# MAXIM-ADC.net
KiCad netlist of a schematic drawn in Altium Designer
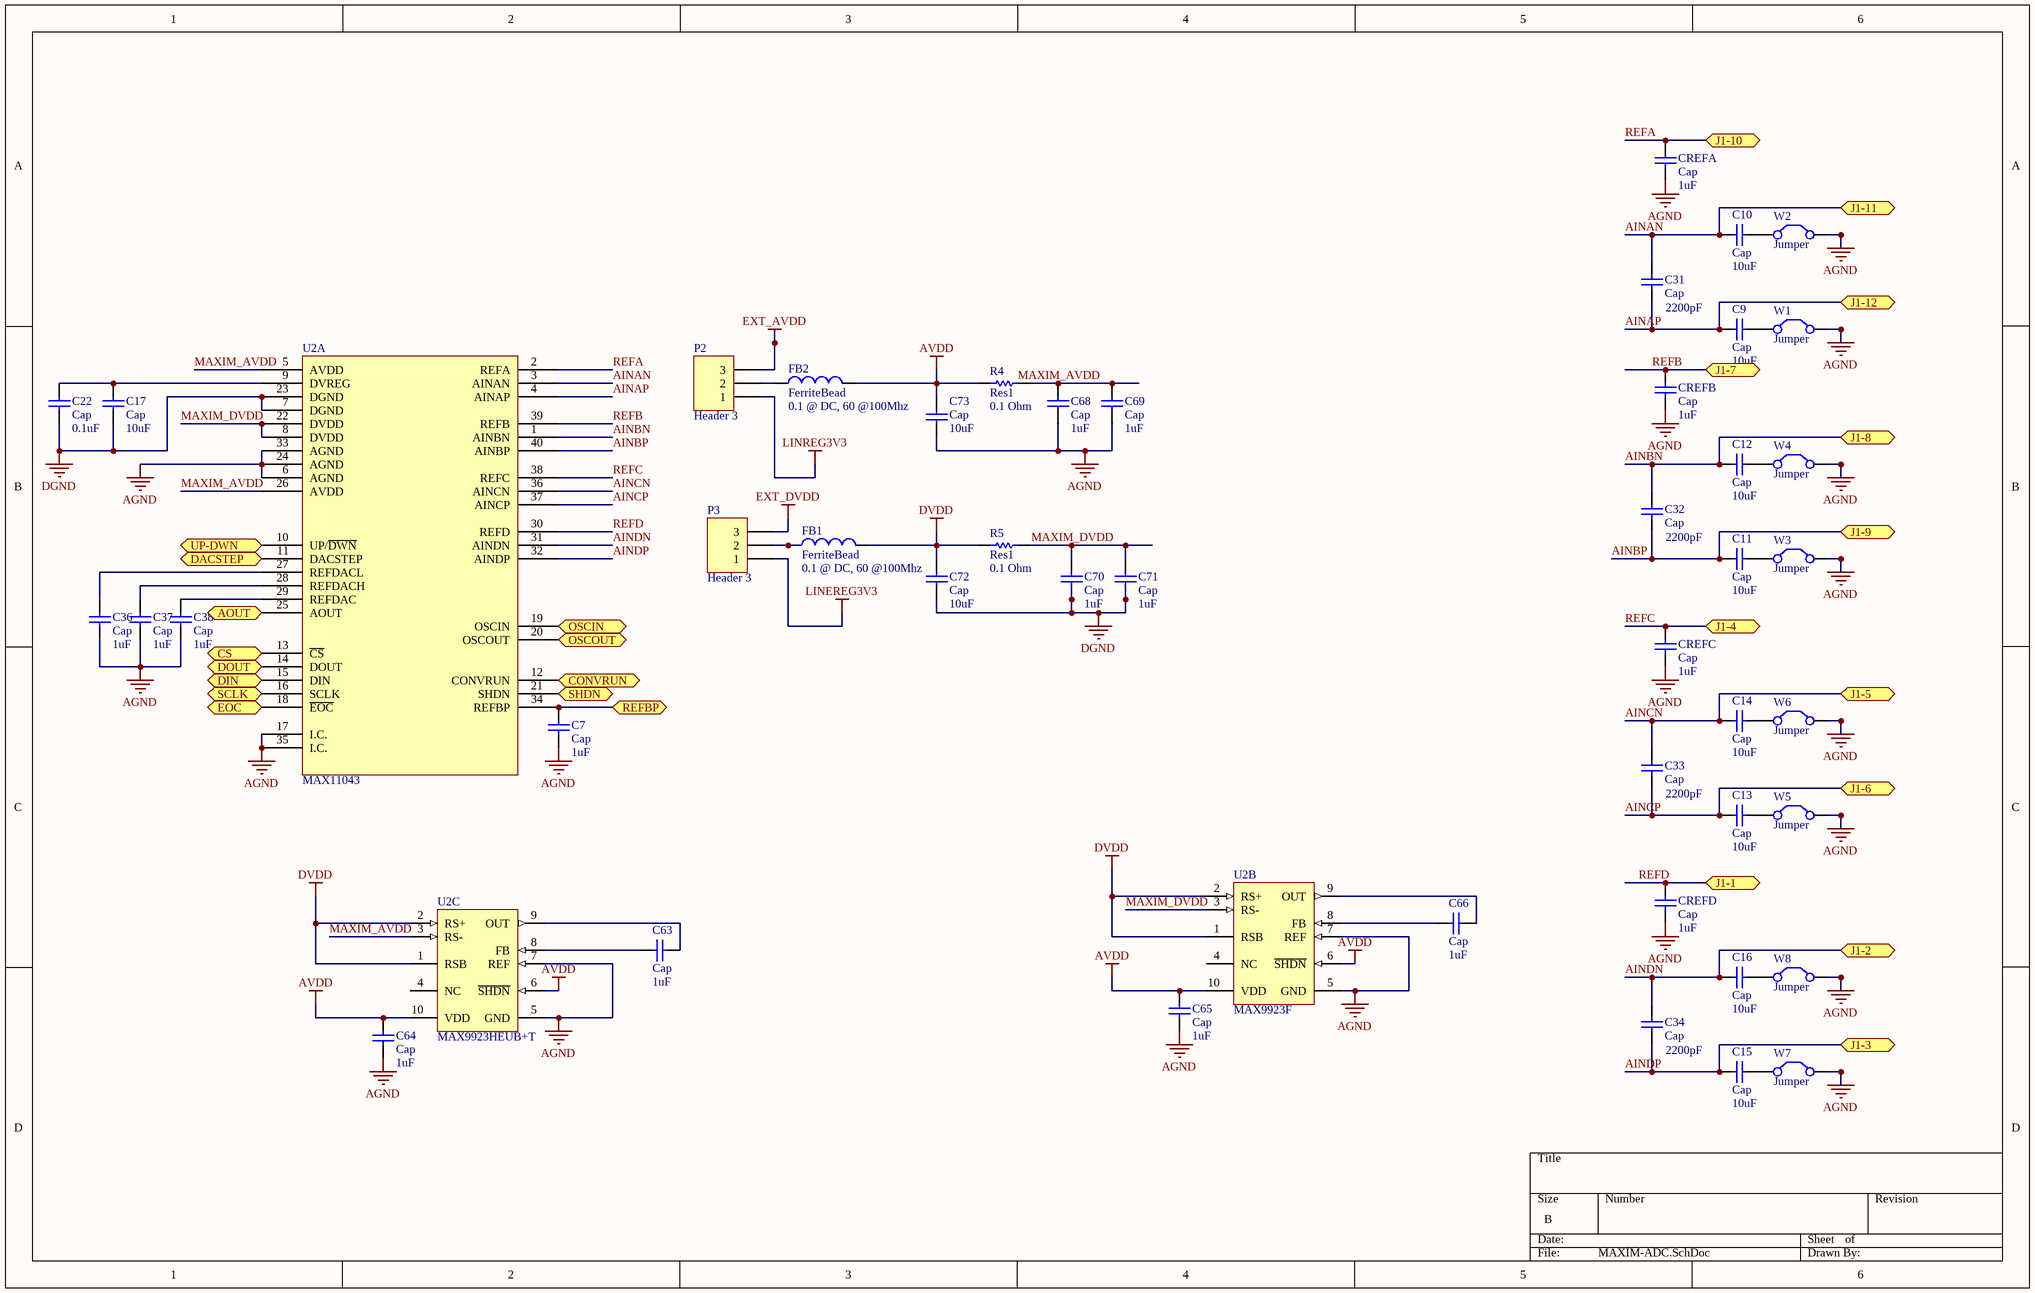
[diagram p0: MAXIM-ADC.SchDoc]

(export (version "E")
  (design (tool "Eeschema 10.0.6"))
  (components
    (comp (ref "C7")
      (value "Cap")
      (footprint "RAD-0.3")
      (description "Capacitor")
      (fields (field (name "ALTIUM_VALUE") "1uF") (field (name "PUBLISHER") "Altium Limited"))
      (libsource (lib "Miscellaneous Devices") (part "Cap"))
    )
    (comp (ref "C9")
      (value "Cap")
      (footprint "RAD-0.3")
      (description "Capacitor")
      (fields (field (name "ALTIUM_VALUE") "10uF") (field (name "PUBLISHER") "Altium Limited"))
      (libsource (lib "Miscellaneous Devices") (part "Cap"))
    )
    (comp (ref "C10")
      (value "Cap")
      (footprint "RAD-0.3")
      (description "Capacitor")
      (fields (field (name "ALTIUM_VALUE") "10uF") (field (name "PUBLISHER") "Altium Limited"))
      (libsource (lib "Miscellaneous Devices") (part "Cap"))
    )
    (comp (ref "C11")
      (value "Cap")
      (footprint "RAD-0.3")
      (description "Capacitor")
      (fields (field (name "ALTIUM_VALUE") "10uF") (field (name "PUBLISHER") "Altium Limited"))
      (libsource (lib "Miscellaneous Devices") (part "Cap"))
    )
    (comp (ref "C12")
      (value "Cap")
      (footprint "RAD-0.3")
      (description "Capacitor")
      (fields (field (name "ALTIUM_VALUE") "10uF") (field (name "PUBLISHER") "Altium Limited"))
      (libsource (lib "Miscellaneous Devices") (part "Cap"))
    )
    (comp (ref "C13")
      (value "Cap")
      (footprint "RAD-0.3")
      (description "Capacitor")
      (fields (field (name "ALTIUM_VALUE") "10uF") (field (name "PUBLISHER") "Altium Limited"))
      (libsource (lib "Miscellaneous Devices") (part "Cap"))
    )
    (comp (ref "C14")
      (value "Cap")
      (footprint "RAD-0.3")
      (description "Capacitor")
      (fields (field (name "ALTIUM_VALUE") "10uF") (field (name "PUBLISHER") "Altium Limited"))
      (libsource (lib "Miscellaneous Devices") (part "Cap"))
    )
    (comp (ref "C15")
      (value "Cap")
      (footprint "RAD-0.3")
      (description "Capacitor")
      (fields (field (name "ALTIUM_VALUE") "10uF") (field (name "PUBLISHER") "Altium Limited"))
      (libsource (lib "Miscellaneous Devices") (part "Cap"))
    )
    (comp (ref "C16")
      (value "Cap")
      (footprint "RAD-0.3")
      (description "Capacitor")
      (fields (field (name "ALTIUM_VALUE") "10uF") (field (name "PUBLISHER") "Altium Limited"))
      (libsource (lib "Miscellaneous Devices") (part "Cap"))
    )
    (comp (ref "C17")
      (value "Cap")
      (footprint "RAD-0.3")
      (description "Capacitor")
      (fields (field (name "ALTIUM_VALUE") "10uF") (field (name "PUBLISHER") "Altium Limited"))
      (libsource (lib "Miscellaneous Devices") (part "Cap"))
    )
    (comp (ref "C22")
      (value "Cap")
      (footprint "RAD-0.3")
      (description "Capacitor")
      (fields (field (name "ALTIUM_VALUE") "0.1uF") (field (name "PUBLISHER") "Altium Limited"))
      (libsource (lib "Miscellaneous Devices") (part "Cap"))
    )
    (comp (ref "C31")
      (value "Cap")
      (footprint "RAD-0.3")
      (description "Capacitor")
      (fields (field (name "ALTIUM_VALUE") "2200pF") (field (name "PUBLISHER") "Altium Limited"))
      (libsource (lib "Miscellaneous Devices") (part "Cap"))
    )
    (comp (ref "C32")
      (value "Cap")
      (footprint "RAD-0.3")
      (description "Capacitor")
      (fields (field (name "ALTIUM_VALUE") "2200pF") (field (name "PUBLISHER") "Altium Limited"))
      (libsource (lib "Miscellaneous Devices") (part "Cap"))
    )
    (comp (ref "C33")
      (value "Cap")
      (footprint "RAD-0.3")
      (description "Capacitor")
      (fields (field (name "ALTIUM_VALUE") "2200pF") (field (name "PUBLISHER") "Altium Limited"))
      (libsource (lib "Miscellaneous Devices") (part "Cap"))
    )
    (comp (ref "C34")
      (value "Cap")
      (footprint "RAD-0.3")
      (description "Capacitor")
      (fields (field (name "ALTIUM_VALUE") "2200pF") (field (name "PUBLISHER") "Altium Limited"))
      (libsource (lib "Miscellaneous Devices") (part "Cap"))
    )
    (comp (ref "C36")
      (value "Cap")
      (footprint "RAD-0.3")
      (description "Capacitor")
      (fields (field (name "ALTIUM_VALUE") "1uF") (field (name "PUBLISHER") "Altium Limited"))
      (libsource (lib "Miscellaneous Devices") (part "Cap"))
    )
    (comp (ref "C37")
      (value "Cap")
      (footprint "RAD-0.3")
      (description "Capacitor")
      (fields (field (name "ALTIUM_VALUE") "1uF") (field (name "PUBLISHER") "Altium Limited"))
      (libsource (lib "Miscellaneous Devices") (part "Cap"))
    )
    (comp (ref "C38")
      (value "Cap")
      (footprint "RAD-0.3")
      (description "Capacitor")
      (fields (field (name "ALTIUM_VALUE") "1uF") (field (name "PUBLISHER") "Altium Limited"))
      (libsource (lib "Miscellaneous Devices") (part "Cap"))
    )
    (comp (ref "C63")
      (value "Cap")
      (footprint "RAD-0.3")
      (description "Capacitor")
      (fields (field (name "ALTIUM_VALUE") "1uF") (field (name "PUBLISHER") "Altium Limited"))
      (libsource (lib "Miscellaneous Devices") (part "Cap"))
    )
    (comp (ref "C64")
      (value "Cap")
      (footprint "RAD-0.3")
      (description "Capacitor")
      (fields (field (name "ALTIUM_VALUE") "1uF") (field (name "PUBLISHER") "Altium Limited"))
      (libsource (lib "Miscellaneous Devices") (part "Cap"))
    )
    (comp (ref "C65")
      (value "Cap")
      (footprint "RAD-0.3")
      (description "Capacitor")
      (fields (field (name "ALTIUM_VALUE") "1uF") (field (name "PUBLISHER") "Altium Limited"))
      (libsource (lib "Miscellaneous Devices") (part "Cap"))
    )
    (comp (ref "C66")
      (value "Cap")
      (footprint "RAD-0.3")
      (description "Capacitor")
      (fields (field (name "ALTIUM_VALUE") "1uF") (field (name "PUBLISHER") "Altium Limited"))
      (libsource (lib "Miscellaneous Devices") (part "Cap"))
    )
    (comp (ref "C68")
      (value "Cap")
      (footprint "0603")
      (description "Capacitor")
      (fields (field (name "ALTIUM_VALUE") "1uF") (field (name "PUBLISHER") "Altium Limited"))
      (libsource (lib "Miscellaneous Devices") (part "Cap"))
    )
    (comp (ref "C69")
      (value "Cap")
      (footprint "RAD-0.3")
      (description "Capacitor")
      (fields (field (name "ALTIUM_VALUE") "1uF") (field (name "PUBLISHER") "Altium Limited"))
      (libsource (lib "Miscellaneous Devices") (part "Cap"))
    )
    (comp (ref "C70")
      (value "Cap")
      (footprint "RAD-0.3")
      (description "Capacitor")
      (fields (field (name "ALTIUM_VALUE") "1uF") (field (name "PUBLISHER") "Altium Limited"))
      (libsource (lib "Miscellaneous Devices") (part "Cap"))
    )
    (comp (ref "C71")
      (value "Cap")
      (footprint "RAD-0.3")
      (description "Capacitor")
      (fields (field (name "ALTIUM_VALUE") "1uF") (field (name "PUBLISHER") "Altium Limited"))
      (libsource (lib "Miscellaneous Devices") (part "Cap"))
    )
    (comp (ref "C72")
      (value "Cap")
      (footprint "RAD-0.3")
      (description "Capacitor")
      (fields (field (name "ALTIUM_VALUE") "10uF") (field (name "PUBLISHER") "Altium Limited"))
      (libsource (lib "Miscellaneous Devices") (part "Cap"))
    )
    (comp (ref "C73")
      (value "Cap")
      (footprint "RAD-0.3")
      (description "Capacitor")
      (fields (field (name "ALTIUM_VALUE") "10uF") (field (name "PUBLISHER") "Altium Limited"))
      (libsource (lib "Miscellaneous Devices") (part "Cap"))
    )
    (comp (ref "CREFA")
      (value "Cap")
      (footprint "RAD-0.3")
      (description "Capacitor")
      (fields (field (name "ALTIUM_VALUE") "1uF") (field (name "PUBLISHER") "Altium Limited"))
      (libsource (lib "Miscellaneous Devices") (part "Cap"))
    )
    (comp (ref "CREFB")
      (value "Cap")
      (footprint "RAD-0.3")
      (description "Capacitor")
      (fields (field (name "ALTIUM_VALUE") "1uF") (field (name "PUBLISHER") "Altium Limited"))
      (libsource (lib "Miscellaneous Devices") (part "Cap"))
    )
    (comp (ref "CREFC")
      (value "Cap")
      (footprint "RAD-0.3")
      (description "Capacitor")
      (fields (field (name "ALTIUM_VALUE") "1uF") (field (name "PUBLISHER") "Altium Limited"))
      (libsource (lib "Miscellaneous Devices") (part "Cap"))
    )
    (comp (ref "CREFD")
      (value "Cap")
      (footprint "RAD-0.3")
      (description "Capacitor")
      (fields (field (name "ALTIUM_VALUE") "1uF") (field (name "PUBLISHER") "Altium Limited"))
      (libsource (lib "Miscellaneous Devices") (part "Cap"))
    )
    (comp (ref "FB1")
      (value "FerriteBead")
      (footprint "0603")
      (description "Inductor")
      (fields
        (field (name "ALTIUM_VALUE") "0.1 @ DC, 60 @100Mhz")
        (field (name "PUBLISHER") "Altium Limited")
      )
      (libsource (lib "Miscellaneous Devices") (part "Inductor"))
    )
    (comp (ref "FB2")
      (value "FerriteBead")
      (footprint "0603")
      (description "Inductor")
      (fields
        (field (name "ALTIUM_VALUE") "0.1 @ DC, 60 @100Mhz")
        (field (name "PUBLISHER") "Altium Limited")
      )
      (libsource (lib "Miscellaneous Devices") (part "Inductor"))
    )
    (comp (ref "P2")
      (value "Header 3")
      (footprint "HDR1X3")
      (description "Header, 3-Pin")
      (fields (field (name "PUBLISHER") "Altium Limited"))
      (libsource (lib "Miscellaneous Connectors") (part "Header 3"))
    )
    (comp (ref "P3")
      (value "Header 3")
      (footprint "HDR1X3")
      (description "Header, 3-Pin")
      (fields (field (name "PUBLISHER") "Altium Limited"))
      (libsource (lib "Miscellaneous Connectors") (part "Header 3"))
    )
    (comp (ref "R4")
      (value "Res1")
      (footprint "AXIAL-0.3")
      (description "Resistor")
      (fields (field (name "ALTIUM_VALUE") "0.1 Ohm") (field (name "PUBLISHER") "Altium Limited"))
      (libsource (lib "Miscellaneous Devices") (part "Res1"))
    )
    (comp (ref "R5")
      (value "Res1")
      (footprint "AXIAL-0.3")
      (description "Resistor")
      (fields (field (name "ALTIUM_VALUE") "0.1 Ohm") (field (name "PUBLISHER") "Altium Limited"))
      (libsource (lib "Miscellaneous Devices") (part "Res1"))
    )
    (comp (ref "U2A") (value "MAX11043") (libsource (lib "Max11043") (part "MAX11043")))
    (comp (ref "U2B")
      (value "MAX9923F")
      (footprint "MAXM-U10+2_N")
      (fields (field (name "PARTNUMBER") "MAX9923HEUB+T"))
      (libsource (lib "Altium Content Vault") (part "MAX992X-U10+2"))
    )
    (comp (ref "U2C")
      (value "MAX9923HEUB+T")
      (footprint "MAXM-U10+2_N")
      (libsource (lib "Altium Content Vault") (part "MAX992X-U10+2"))
    )
    (comp (ref "W1")
      (value "Jumper")
      (footprint "RAD-0.2")
      (description "Jumper Wire")
      (fields (field (name "PUBLISHER") "Altium Limited"))
      (libsource (lib "Miscellaneous Devices") (part "Jumper"))
    )
    (comp (ref "W2")
      (value "Jumper")
      (footprint "RAD-0.2")
      (description "Jumper Wire")
      (fields (field (name "PUBLISHER") "Altium Limited"))
      (libsource (lib "Miscellaneous Devices") (part "Jumper"))
    )
    (comp (ref "W3")
      (value "Jumper")
      (footprint "RAD-0.2")
      (description "Jumper Wire")
      (fields (field (name "PUBLISHER") "Altium Limited"))
      (libsource (lib "Miscellaneous Devices") (part "Jumper"))
    )
    (comp (ref "W4")
      (value "Jumper")
      (footprint "RAD-0.2")
      (description "Jumper Wire")
      (fields (field (name "PUBLISHER") "Altium Limited"))
      (libsource (lib "Miscellaneous Devices") (part "Jumper"))
    )
    (comp (ref "W5")
      (value "Jumper")
      (footprint "RAD-0.2")
      (description "Jumper Wire")
      (fields (field (name "PUBLISHER") "Altium Limited"))
      (libsource (lib "Miscellaneous Devices") (part "Jumper"))
    )
    (comp (ref "W6")
      (value "Jumper")
      (footprint "RAD-0.2")
      (description "Jumper Wire")
      (fields (field (name "PUBLISHER") "Altium Limited"))
      (libsource (lib "Miscellaneous Devices") (part "Jumper"))
    )
    (comp (ref "W7")
      (value "Jumper")
      (footprint "RAD-0.2")
      (description "Jumper Wire")
      (fields (field (name "PUBLISHER") "Altium Limited"))
      (libsource (lib "Miscellaneous Devices") (part "Jumper"))
    )
    (comp (ref "W8")
      (value "Jumper")
      (footprint "RAD-0.2")
      (description "Jumper Wire")
      (fields (field (name "PUBLISHER") "Altium Limited"))
      (libsource (lib "Miscellaneous Devices") (part "Jumper"))
    )
  )
  (nets
    (net (code "1") (name "/AINAN") (class "Default")
      (node (ref "C10") (pin "2") (pinfunction "2_2") (pintype "passive"))
      (node (ref "C31") (pin "2") (pinfunction "2_2") (pintype "passive"))
      (node (ref "U2A") (pin "3") (pinfunction "AINAN_3") (pintype "passive"))
    )
    (net (code "2") (name "/AINAP") (class "Default")
      (node (ref "C31") (pin "1") (pinfunction "1_1") (pintype "passive"))
      (node (ref "C9") (pin "2") (pinfunction "2_2") (pintype "passive"))
      (node (ref "U2A") (pin "4") (pinfunction "AINAP_4") (pintype "passive"))
    )
    (net (code "3") (name "/AINBN") (class "Default")
      (node (ref "C12") (pin "2") (pinfunction "2_2") (pintype "passive"))
      (node (ref "C32") (pin "2") (pinfunction "2_2") (pintype "passive"))
      (node (ref "U2A") (pin "1") (pinfunction "AINBN_1") (pintype "passive"))
    )
    (net (code "4") (name "/AINBP") (class "Default")
      (node (ref "C11") (pin "2") (pinfunction "2_2") (pintype "passive"))
      (node (ref "C32") (pin "1") (pinfunction "1_1") (pintype "passive"))
      (node (ref "U2A") (pin "40") (pinfunction "AINBP_40") (pintype "passive"))
    )
    (net (code "5") (name "/AINCN") (class "Default")
      (node (ref "C14") (pin "2") (pinfunction "2_2") (pintype "passive"))
      (node (ref "C33") (pin "2") (pinfunction "2_2") (pintype "passive"))
      (node (ref "U2A") (pin "36") (pinfunction "AINCN_36") (pintype "passive"))
    )
    (net (code "6") (name "/AINCP") (class "Default")
      (node (ref "C13") (pin "2") (pinfunction "2_2") (pintype "passive"))
      (node (ref "C33") (pin "1") (pinfunction "1_1") (pintype "passive"))
      (node (ref "U2A") (pin "37") (pinfunction "AINCP_37") (pintype "passive"))
    )
    (net (code "7") (name "/AINDN") (class "Default")
      (node (ref "C16") (pin "2") (pinfunction "2_2") (pintype "passive"))
      (node (ref "C34") (pin "2") (pinfunction "2_2") (pintype "passive"))
      (node (ref "U2A") (pin "31") (pinfunction "AINDN_31") (pintype "passive"))
    )
    (net (code "8") (name "/AINDP") (class "Default")
      (node (ref "C15") (pin "2") (pinfunction "2_2") (pintype "passive"))
      (node (ref "C34") (pin "1") (pinfunction "1_1") (pintype "passive"))
      (node (ref "U2A") (pin "32") (pinfunction "AINDP_32") (pintype "passive"))
    )
    (net (code "9") (name "/AOUT") (class "Default")
      (node (ref "U2A") (pin "25") (pinfunction "AOUT_25") (pintype "passive"))
    )
    (net (code "10") (name "/CONVRUN") (class "Default")
      (node (ref "U2A") (pin "12") (pinfunction "CONVRUN_12") (pintype "passive"))
    )
    (net (code "11") (name "/CS") (class "Default")
      (node (ref "U2A") (pin "13") (pinfunction "~{CS}_13") (pintype "passive"))
    )
    (net (code "12") (name "/DACSTEP") (class "Default")
      (node (ref "U2A") (pin "11") (pinfunction "DACSTEP_11") (pintype "passive"))
    )
    (net (code "13") (name "/DIN") (class "Default")
      (node (ref "U2A") (pin "15") (pinfunction "DIN_15") (pintype "passive"))
    )
    (net (code "14") (name "/DOUT") (class "Default")
      (node (ref "U2A") (pin "14") (pinfunction "DOUT_14") (pintype "passive"))
    )
    (net (code "15") (name "/EOC") (class "Default")
      (node (ref "U2A") (pin "18") (pinfunction "~{EOC}_18") (pintype "passive"))
    )
    (net (code "16") (name "/MAXIM_AVDD") (class "Default")
      (node (ref "U2A") (pin "26") (pinfunction "AVDD_26") (pintype "passive"))
      (node (ref "U2A") (pin "5") (pinfunction "AVDD_5") (pintype "passive"))
      (node (ref "U2C") (pin "3") (pinfunction "RS-_3") (pintype "input"))
    )
    (net (code "17") (name "/MAXIM_DVDD") (class "Default")
      (node (ref "C70") (pin "1") (pinfunction "1_1") (pintype "passive"))
      (node (ref "C71") (pin "1") (pinfunction "1_1") (pintype "passive"))
      (node (ref "R5") (pin "1") (pinfunction "1_1") (pintype "passive"))
      (node (ref "U2A") (pin "22") (pinfunction "DVDD_22") (pintype "passive"))
      (node (ref "U2A") (pin "8") (pinfunction "DVDD_8") (pintype "passive"))
      (node (ref "U2B") (pin "3") (pinfunction "RS-_3") (pintype "input"))
    )
    (net (code "18") (name "/OSCIN") (class "Default")
      (node (ref "U2A") (pin "19") (pinfunction "OSCIN_19") (pintype "passive"))
    )
    (net (code "19") (name "/OSCOUT") (class "Default")
      (node (ref "U2A") (pin "20") (pinfunction "OSCOUT_20") (pintype "passive"))
    )
    (net (code "20") (name "/REFA") (class "Default")
      (node (ref "CREFA") (pin "2") (pinfunction "2_2") (pintype "passive"))
      (node (ref "U2A") (pin "2") (pinfunction "REFA_2") (pintype "passive"))
    )
    (net (code "21") (name "/REFB") (class "Default")
      (node (ref "CREFB") (pin "2") (pinfunction "2_2") (pintype "passive"))
      (node (ref "U2A") (pin "39") (pinfunction "REFB_39") (pintype "passive"))
    )
    (net (code "22") (name "/REFBP") (class "Default")
      (node (ref "C7") (pin "1") (pinfunction "1_1") (pintype "passive"))
      (node (ref "U2A") (pin "34") (pinfunction "REFBP_34") (pintype "passive"))
    )
    (net (code "23") (name "/REFC") (class "Default")
      (node (ref "CREFC") (pin "2") (pinfunction "2_2") (pintype "passive"))
      (node (ref "U2A") (pin "38") (pinfunction "REFC_38") (pintype "passive"))
    )
    (net (code "24") (name "/REFD") (class "Default")
      (node (ref "CREFD") (pin "2") (pinfunction "2_2") (pintype "passive"))
      (node (ref "U2A") (pin "30") (pinfunction "REFD_30") (pintype "passive"))
    )
    (net (code "25") (name "/SCLK") (class "Default")
      (node (ref "U2A") (pin "16") (pinfunction "SCLK_16") (pintype "passive"))
    )
    (net (code "26") (name "/SHDN") (class "Default")
      (node (ref "U2A") (pin "21") (pinfunction "SHDN_21") (pintype "passive"))
    )
    (net (code "27") (name "/UP-DWN") (class "Default")
      (node (ref "U2A") (pin "10") (pinfunction "UP/~{DWN}_10") (pintype "passive"))
    )
    (net (code "28") (name "AGND") (class "Default")
      (node (ref "C36") (pin "1") (pinfunction "1_1") (pintype "passive"))
      (node (ref "C37") (pin "2") (pinfunction "2_2") (pintype "passive"))
      (node (ref "C38") (pin "1") (pinfunction "1_1") (pintype "passive"))
      (node (ref "C64") (pin "1") (pinfunction "1_1") (pintype "passive"))
      (node (ref "C65") (pin "1") (pinfunction "1_1") (pintype "passive"))
      (node (ref "C68") (pin "2") (pinfunction "2_2") (pintype "passive"))
      (node (ref "C69") (pin "2") (pinfunction "2_2") (pintype "passive"))
      (node (ref "C7") (pin "2") (pinfunction "2_2") (pintype "passive"))
      (node (ref "C73") (pin "2") (pinfunction "2_2") (pintype "passive"))
      (node (ref "CREFA") (pin "1") (pinfunction "1_1") (pintype "passive"))
      (node (ref "CREFB") (pin "1") (pinfunction "1_1") (pintype "passive"))
      (node (ref "CREFC") (pin "1") (pinfunction "1_1") (pintype "passive"))
      (node (ref "CREFD") (pin "1") (pinfunction "1_1") (pintype "passive"))
      (node (ref "U2A") (pin "17") (pinfunction "I.C._17") (pintype "passive"))
      (node (ref "U2A") (pin "24") (pinfunction "AGND_24") (pintype "passive"))
      (node (ref "U2A") (pin "33") (pinfunction "AGND_33") (pintype "passive"))
      (node (ref "U2A") (pin "35") (pinfunction "I.C._35") (pintype "passive"))
      (node (ref "U2A") (pin "6") (pinfunction "AGND_6") (pintype "passive"))
      (node (ref "U2B") (pin "5") (pinfunction "GND_5") (pintype "power_in"))
      (node (ref "U2B") (pin "7") (pinfunction "REF_7") (pintype "input"))
      (node (ref "U2C") (pin "5") (pinfunction "GND_5") (pintype "power_in"))
      (node (ref "U2C") (pin "7") (pinfunction "REF_7") (pintype "input"))
      (node (ref "W1") (pin "2") (pinfunction "C2_2") (pintype "passive"))
      (node (ref "W2") (pin "2") (pinfunction "C2_2") (pintype "passive"))
      (node (ref "W3") (pin "2") (pinfunction "C2_2") (pintype "passive"))
      (node (ref "W4") (pin "2") (pinfunction "C2_2") (pintype "passive"))
      (node (ref "W5") (pin "2") (pinfunction "C2_2") (pintype "passive"))
      (node (ref "W6") (pin "2") (pinfunction "C2_2") (pintype "passive"))
      (node (ref "W7") (pin "2") (pinfunction "C2_2") (pintype "passive"))
      (node (ref "W8") (pin "2") (pinfunction "C2_2") (pintype "passive"))
    )
    (net (code "29") (name "AVDD") (class "Default")
      (node (ref "C64") (pin "2") (pinfunction "2_2") (pintype "passive"))
      (node (ref "C65") (pin "2") (pinfunction "2_2") (pintype "passive"))
      (node (ref "C73") (pin "1") (pinfunction "1_1") (pintype "passive"))
      (node (ref "FB2") (pin "2") (pinfunction "2_2") (pintype "passive"))
      (node (ref "R4") (pin "2") (pinfunction "2_2") (pintype "passive"))
      (node (ref "U2B") (pin "10") (pinfunction "VDD_10") (pintype "power_in"))
      (node (ref "U2B") (pin "6") (pinfunction "~{SHDN}_6") (pintype "input"))
      (node (ref "U2C") (pin "10") (pinfunction "VDD_10") (pintype "power_in"))
      (node (ref "U2C") (pin "6") (pinfunction "~{SHDN}_6") (pintype "input"))
    )
    (net (code "30") (name "DGND") (class "Default")
      (node (ref "C17") (pin "2") (pinfunction "2_2") (pintype "passive"))
      (node (ref "C22") (pin "2") (pinfunction "2_2") (pintype "passive"))
      (node (ref "C70") (pin "2") (pinfunction "2_2") (pintype "passive"))
      (node (ref "C71") (pin "2") (pinfunction "2_2") (pintype "passive"))
      (node (ref "C72") (pin "2") (pinfunction "2_2") (pintype "passive"))
      (node (ref "U2A") (pin "23") (pinfunction "DGND_23") (pintype "passive"))
      (node (ref "U2A") (pin "7") (pinfunction "DGND_7") (pintype "passive"))
    )
    (net (code "31") (name "DVDD") (class "Default")
      (node (ref "C72") (pin "1") (pinfunction "1_1") (pintype "passive"))
      (node (ref "FB1") (pin "2") (pinfunction "2_2") (pintype "passive"))
      (node (ref "R5") (pin "2") (pinfunction "2_2") (pintype "passive"))
      (node (ref "U2B") (pin "1") (pinfunction "RSB_1") (pintype "power_in"))
      (node (ref "U2B") (pin "2") (pinfunction "RS+_2") (pintype "input"))
      (node (ref "U2C") (pin "1") (pinfunction "RSB_1") (pintype "power_in"))
      (node (ref "U2C") (pin "2") (pinfunction "RS+_2") (pintype "input"))
    )
    (net (code "32") (name "EXT_AVDD") (class "Default")
      (node (ref "P2") (pin "3") (pinfunction "3_3") (pintype "passive"))
    )
    (net (code "33") (name "EXT_DVDD") (class "Default")
      (node (ref "P3") (pin "3") (pinfunction "3_3") (pintype "passive"))
    )
    (net (code "34") (name "LINEREG3V3") (class "Default")
      (node (ref "P3") (pin "1") (pinfunction "1_1") (pintype "passive"))
    )
    (net (code "35") (name "LINREG3V3") (class "Default")
      (node (ref "P2") (pin "1") (pinfunction "1_1") (pintype "passive"))
    )
    (net (code "36") (name "Net-(C68-Pad1)") (class "Default")
      (node (ref "C68") (pin "1") (pinfunction "1_1") (pintype "passive"))
      (node (ref "C69") (pin "1") (pinfunction "1_1") (pintype "passive"))
      (node (ref "R4") (pin "1") (pinfunction "1_1") (pintype "passive"))
    )
    (net (code "37") (name "Net-(FB1-Pad1)") (class "Default")
      (node (ref "FB1") (pin "1") (pinfunction "1_1") (pintype "passive"))
      (node (ref "P3") (pin "2") (pinfunction "2_2") (pintype "passive"))
    )
    (net (code "38") (name "Net-(FB2-Pad1)") (class "Default")
      (node (ref "FB2") (pin "1") (pinfunction "1_1") (pintype "passive"))
      (node (ref "P2") (pin "2") (pinfunction "2_2") (pintype "passive"))
    )
    (net (code "39") (name "Net-(U2A-DVREG)") (class "Default")
      (node (ref "C17") (pin "1") (pinfunction "1_1") (pintype "passive"))
      (node (ref "C22") (pin "1") (pinfunction "1_1") (pintype "passive"))
      (node (ref "U2A") (pin "9") (pinfunction "DVREG_9") (pintype "passive"))
    )
    (net (code "40") (name "Net-(U2A-REFDAC)") (class "Default")
      (node (ref "C38") (pin "2") (pinfunction "2_2") (pintype "passive"))
      (node (ref "U2A") (pin "29") (pinfunction "REFDAC_29") (pintype "passive"))
    )
    (net (code "41") (name "Net-(U2A-REFDACH)") (class "Default")
      (node (ref "C37") (pin "1") (pinfunction "1_1") (pintype "passive"))
      (node (ref "U2A") (pin "28") (pinfunction "REFDACH_28") (pintype "passive"))
    )
    (net (code "42") (name "Net-(U2A-REFDACL)") (class "Default")
      (node (ref "C36") (pin "2") (pinfunction "2_2") (pintype "passive"))
      (node (ref "U2A") (pin "27") (pinfunction "REFDACL_27") (pintype "passive"))
    )
    (net (code "43") (name "Net-(U2B-FB)") (class "Default")
      (node (ref "C66") (pin "1") (pinfunction "1_1") (pintype "passive"))
      (node (ref "U2B") (pin "8") (pinfunction "FB_8") (pintype "input"))
    )
    (net (code "44") (name "Net-(U2B-OUT)") (class "Default")
      (node (ref "C66") (pin "2") (pinfunction "2_2") (pintype "passive"))
      (node (ref "U2B") (pin "9") (pinfunction "OUT_9") (pintype "output"))
    )
    (net (code "45") (name "Net-(U2C-FB)") (class "Default")
      (node (ref "C63") (pin "1") (pinfunction "1_1") (pintype "passive"))
      (node (ref "U2C") (pin "8") (pinfunction "FB_8") (pintype "input"))
    )
    (net (code "46") (name "Net-(U2C-OUT)") (class "Default")
      (node (ref "C63") (pin "2") (pinfunction "2_2") (pintype "passive"))
      (node (ref "U2C") (pin "9") (pinfunction "OUT_9") (pintype "output"))
    )
    (net (code "47") (name "Net-(W1-C1)") (class "Default")
      (node (ref "C9") (pin "1") (pinfunction "1_1") (pintype "passive"))
      (node (ref "W1") (pin "1") (pinfunction "C1_1") (pintype "passive"))
    )
    (net (code "48") (name "Net-(W2-C1)") (class "Default")
      (node (ref "C10") (pin "1") (pinfunction "1_1") (pintype "passive"))
      (node (ref "W2") (pin "1") (pinfunction "C1_1") (pintype "passive"))
    )
    (net (code "49") (name "Net-(W3-C1)") (class "Default")
      (node (ref "C11") (pin "1") (pinfunction "1_1") (pintype "passive"))
      (node (ref "W3") (pin "1") (pinfunction "C1_1") (pintype "passive"))
    )
    (net (code "50") (name "Net-(W4-C1)") (class "Default")
      (node (ref "C12") (pin "1") (pinfunction "1_1") (pintype "passive"))
      (node (ref "W4") (pin "1") (pinfunction "C1_1") (pintype "passive"))
    )
    (net (code "51") (name "Net-(W5-C1)") (class "Default")
      (node (ref "C13") (pin "1") (pinfunction "1_1") (pintype "passive"))
      (node (ref "W5") (pin "1") (pinfunction "C1_1") (pintype "passive"))
    )
    (net (code "52") (name "Net-(W6-C1)") (class "Default")
      (node (ref "C14") (pin "1") (pinfunction "1_1") (pintype "passive"))
      (node (ref "W6") (pin "1") (pinfunction "C1_1") (pintype "passive"))
    )
    (net (code "53") (name "Net-(W7-C1)") (class "Default")
      (node (ref "C15") (pin "1") (pinfunction "1_1") (pintype "passive"))
      (node (ref "W7") (pin "1") (pinfunction "C1_1") (pintype "passive"))
    )
    (net (code "54") (name "Net-(W8-C1)") (class "Default")
      (node (ref "C16") (pin "1") (pinfunction "1_1") (pintype "passive"))
      (node (ref "W8") (pin "1") (pinfunction "C1_1") (pintype "passive"))
    )
    (net (code "55") (name "unconnected-(U2B-NC-Pad4)") (class "Default")
      (node (ref "U2B") (pin "4") (pinfunction "NC_4") (pintype "passive"))
    )
    (net (code "56") (name "unconnected-(U2C-NC-Pad4)") (class "Default")
      (node (ref "U2C") (pin "4") (pinfunction "NC_4") (pintype "passive"))
    )
  )
)
